# Terminierung_RS485_RJ45_Pads.net
KiCad netlist of a schematic drawn in EAGLE
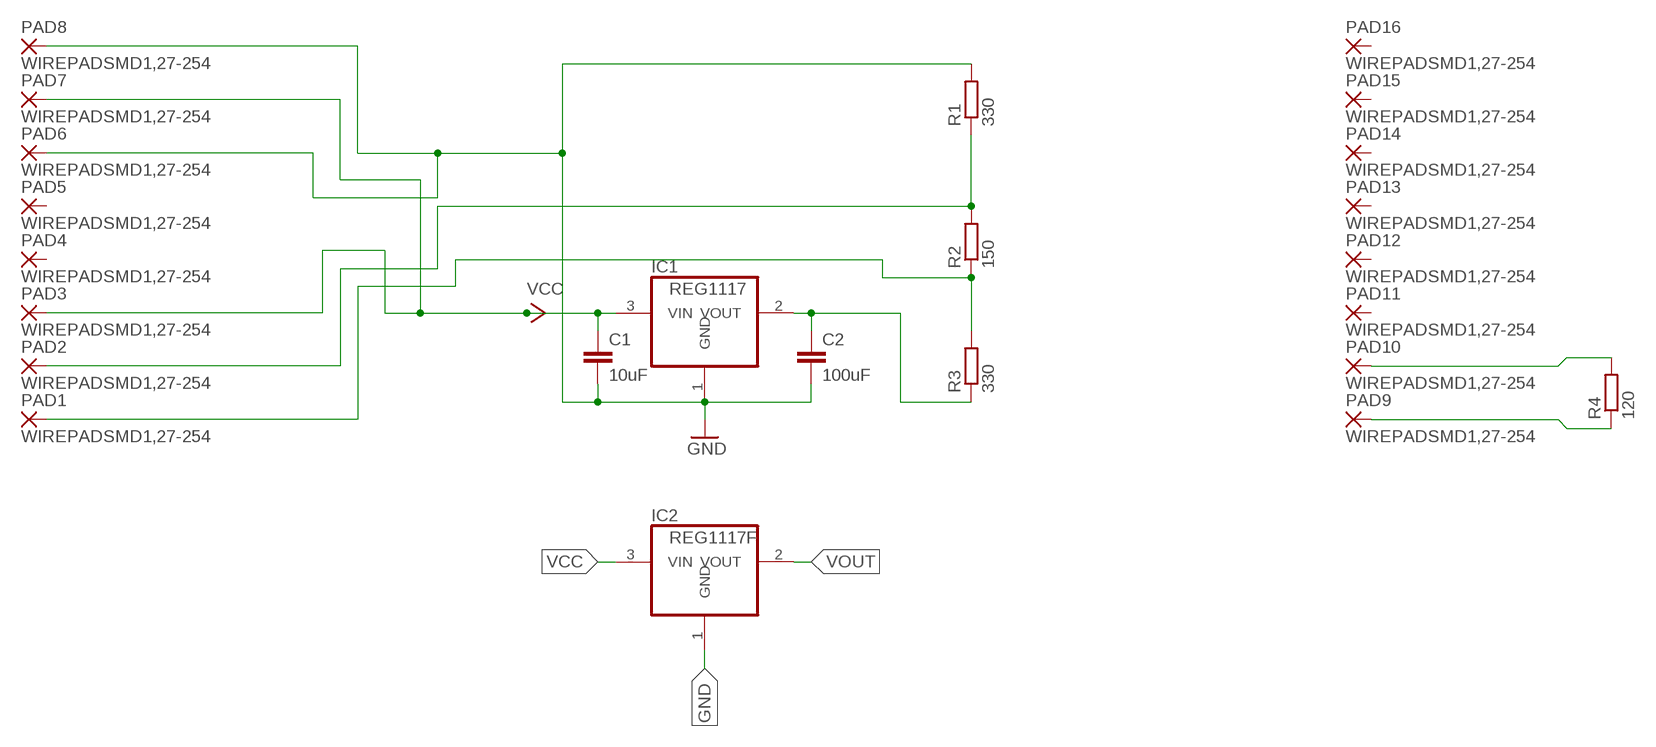
[diagram p0: schematic, sheet 1]

(export (version "E")
  (design (tool "Eeschema 10.0.6"))
  (components
    (comp (ref "C1")
      (value "10uF")
      (footprint "eagle-import:C0805K")
      (libsource (lib "eagle-import") (part "C-EUC0805K"))
    )
    (comp (ref "C2")
      (value "100uF")
      (footprint "eagle-import:C0805K")
      (libsource (lib "eagle-import") (part "C-EUC0805K"))
    )
    (comp (ref "IC1")
      (value "REG1117")
      (footprint "eagle-import:SOT223")
      (libsource (lib "eagle-import") (part "REG1117"))
    )
    (comp (ref "IC2")
      (value "REG1117F")
      (footprint "eagle-import:DD-3")
      (fields (field (name "MF") "TEXAS INSTRUMENTS") (field (name "MPN") "REG1117FAKTTT"))
      (libsource (lib "eagle-import") (part "REG1117F"))
    )
    (comp (ref "PAD1")
      (value "WIREPADSMD1,27-254")
      (footprint "eagle-import:SMD1,27-2,54")
      (libsource (lib "eagle-import") (part "WIREPADSMD1,27-254"))
    )
    (comp (ref "PAD2")
      (value "WIREPADSMD1,27-254")
      (footprint "eagle-import:SMD1,27-2,54")
      (libsource (lib "eagle-import") (part "WIREPADSMD1,27-254"))
    )
    (comp (ref "PAD3")
      (value "WIREPADSMD1,27-254")
      (footprint "eagle-import:SMD1,27-2,54")
      (libsource (lib "eagle-import") (part "WIREPADSMD1,27-254"))
    )
    (comp (ref "PAD4")
      (value "WIREPADSMD1,27-254")
      (footprint "eagle-import:SMD1,27-2,54")
      (libsource (lib "eagle-import") (part "WIREPADSMD1,27-254"))
    )
    (comp (ref "PAD5")
      (value "WIREPADSMD1,27-254")
      (footprint "eagle-import:SMD1,27-2,54")
      (libsource (lib "eagle-import") (part "WIREPADSMD1,27-254"))
    )
    (comp (ref "PAD6")
      (value "WIREPADSMD1,27-254")
      (footprint "eagle-import:SMD1,27-2,54")
      (libsource (lib "eagle-import") (part "WIREPADSMD1,27-254"))
    )
    (comp (ref "PAD7")
      (value "WIREPADSMD1,27-254")
      (footprint "eagle-import:SMD1,27-2,54")
      (libsource (lib "eagle-import") (part "WIREPADSMD1,27-254"))
    )
    (comp (ref "PAD8")
      (value "WIREPADSMD1,27-254")
      (footprint "eagle-import:SMD1,27-2,54")
      (libsource (lib "eagle-import") (part "WIREPADSMD1,27-254"))
    )
    (comp (ref "PAD9")
      (value "WIREPADSMD1,27-254")
      (footprint "eagle-import:SMD1,27-2,54")
      (libsource (lib "eagle-import") (part "WIREPADSMD1,27-254"))
    )
    (comp (ref "PAD10")
      (value "WIREPADSMD1,27-254")
      (footprint "eagle-import:SMD1,27-2,54")
      (libsource (lib "eagle-import") (part "WIREPADSMD1,27-254"))
    )
    (comp (ref "PAD11")
      (value "WIREPADSMD1,27-254")
      (footprint "eagle-import:SMD1,27-2,54")
      (libsource (lib "eagle-import") (part "WIREPADSMD1,27-254"))
    )
    (comp (ref "PAD12")
      (value "WIREPADSMD1,27-254")
      (footprint "eagle-import:SMD1,27-2,54")
      (libsource (lib "eagle-import") (part "WIREPADSMD1,27-254"))
    )
    (comp (ref "PAD13")
      (value "WIREPADSMD1,27-254")
      (footprint "eagle-import:SMD1,27-2,54")
      (libsource (lib "eagle-import") (part "WIREPADSMD1,27-254"))
    )
    (comp (ref "PAD14")
      (value "WIREPADSMD1,27-254")
      (footprint "eagle-import:SMD1,27-2,54")
      (libsource (lib "eagle-import") (part "WIREPADSMD1,27-254"))
    )
    (comp (ref "PAD15")
      (value "WIREPADSMD1,27-254")
      (footprint "eagle-import:SMD1,27-2,54")
      (libsource (lib "eagle-import") (part "WIREPADSMD1,27-254"))
    )
    (comp (ref "PAD16")
      (value "WIREPADSMD1,27-254")
      (footprint "eagle-import:SMD1,27-2,54")
      (libsource (lib "eagle-import") (part "WIREPADSMD1,27-254"))
    )
    (comp (ref "R1")
      (value "330")
      (footprint "eagle-import:R0805")
      (libsource (lib "eagle-import") (part "R-EU_R0805"))
    )
    (comp (ref "R2")
      (value "150")
      (footprint "eagle-import:R0805")
      (libsource (lib "eagle-import") (part "R-EU_R0805"))
    )
    (comp (ref "R3")
      (value "330")
      (footprint "eagle-import:R0805")
      (libsource (lib "eagle-import") (part "R-EU_R0805"))
    )
    (comp (ref "R4")
      (value "120")
      (footprint "eagle-import:R0805")
      (libsource (lib "eagle-import") (part "R-EU_R0805"))
    )
  )
  (nets
    (net (code "1") (name "GND") (class "Default")
      (node (ref "C1") (pin "2") (pinfunction "2_2") (pintype "passive"))
      (node (ref "C2") (pin "2") (pinfunction "2_2") (pintype "passive"))
      (node (ref "IC1") (pin "1") (pinfunction "GND_1") (pintype "power_in"))
      (node (ref "IC2") (pin "1") (pinfunction "GND_1") (pintype "power_in"))
      (node (ref "PAD6") (pin "1") (pinfunction "P_1") (pintype "passive"))
      (node (ref "PAD8") (pin "1") (pinfunction "P_1") (pintype "passive"))
      (node (ref "R1") (pin "2") (pinfunction "2_2") (pintype "passive"))
    )
    (net (code "2") (name "Net-(PAD1-P)") (class "Default")
      (node (ref "PAD1") (pin "1") (pinfunction "P_1") (pintype "passive"))
      (node (ref "R2") (pin "1") (pinfunction "1_1") (pintype "passive"))
      (node (ref "R3") (pin "2") (pinfunction "2_2") (pintype "passive"))
    )
    (net (code "3") (name "Net-(PAD2-P)") (class "Default")
      (node (ref "PAD2") (pin "1") (pinfunction "P_1") (pintype "passive"))
      (node (ref "R1") (pin "1") (pinfunction "1_1") (pintype "passive"))
      (node (ref "R2") (pin "2") (pinfunction "2_2") (pintype "passive"))
    )
    (net (code "4") (name "Net-(PAD9-P)") (class "Default")
      (node (ref "PAD9") (pin "1") (pinfunction "P_1") (pintype "passive"))
      (node (ref "R4") (pin "1") (pinfunction "1_1") (pintype "passive"))
    )
    (net (code "5") (name "Net-(PAD10-P)") (class "Default")
      (node (ref "PAD10") (pin "1") (pinfunction "P_1") (pintype "passive"))
      (node (ref "R4") (pin "2") (pinfunction "2_2") (pintype "passive"))
    )
    (net (code "6") (name "VCC") (class "Default")
      (node (ref "C1") (pin "1") (pinfunction "1_1") (pintype "passive"))
      (node (ref "IC1") (pin "3") (pinfunction "VIN_3") (pintype "input"))
      (node (ref "IC2") (pin "3") (pinfunction "VIN_3") (pintype "input"))
      (node (ref "PAD3") (pin "1") (pinfunction "P_1") (pintype "passive"))
      (node (ref "PAD7") (pin "1") (pinfunction "P_1") (pintype "passive"))
    )
    (net (code "7") (name "VOUT") (class "Default")
      (node (ref "C2") (pin "1") (pinfunction "1_1") (pintype "passive"))
      (node (ref "IC1") (pin "2") (pinfunction "VOUT_2") (pintype "output"))
      (node (ref "IC2") (pin "2") (pinfunction "VOUT_2") (pintype "output"))
      (node (ref "R3") (pin "1") (pinfunction "1_1") (pintype "passive"))
    )
    (net (code "8") (name "unconnected-(PAD4-P-Pad1)") (class "Default")
      (node (ref "PAD4") (pin "1") (pinfunction "P_1") (pintype "passive"))
    )
    (net (code "9") (name "unconnected-(PAD5-P-Pad1)") (class "Default")
      (node (ref "PAD5") (pin "1") (pinfunction "P_1") (pintype "passive"))
    )
    (net (code "10") (name "unconnected-(PAD11-P-Pad1)") (class "Default")
      (node (ref "PAD11") (pin "1") (pinfunction "P_1") (pintype "passive"))
    )
    (net (code "11") (name "unconnected-(PAD12-P-Pad1)") (class "Default")
      (node (ref "PAD12") (pin "1") (pinfunction "P_1") (pintype "passive"))
    )
    (net (code "12") (name "unconnected-(PAD13-P-Pad1)") (class "Default")
      (node (ref "PAD13") (pin "1") (pinfunction "P_1") (pintype "passive"))
    )
    (net (code "13") (name "unconnected-(PAD14-P-Pad1)") (class "Default")
      (node (ref "PAD14") (pin "1") (pinfunction "P_1") (pintype "passive"))
    )
    (net (code "14") (name "unconnected-(PAD15-P-Pad1)") (class "Default")
      (node (ref "PAD15") (pin "1") (pinfunction "P_1") (pintype "passive"))
    )
    (net (code "15") (name "unconnected-(PAD16-P-Pad1)") (class "Default")
      (node (ref "PAD16") (pin "1") (pinfunction "P_1") (pintype "passive"))
    )
  )
)
